# FeatherBME280.net
KiCad netlist of a schematic drawn in EAGLE
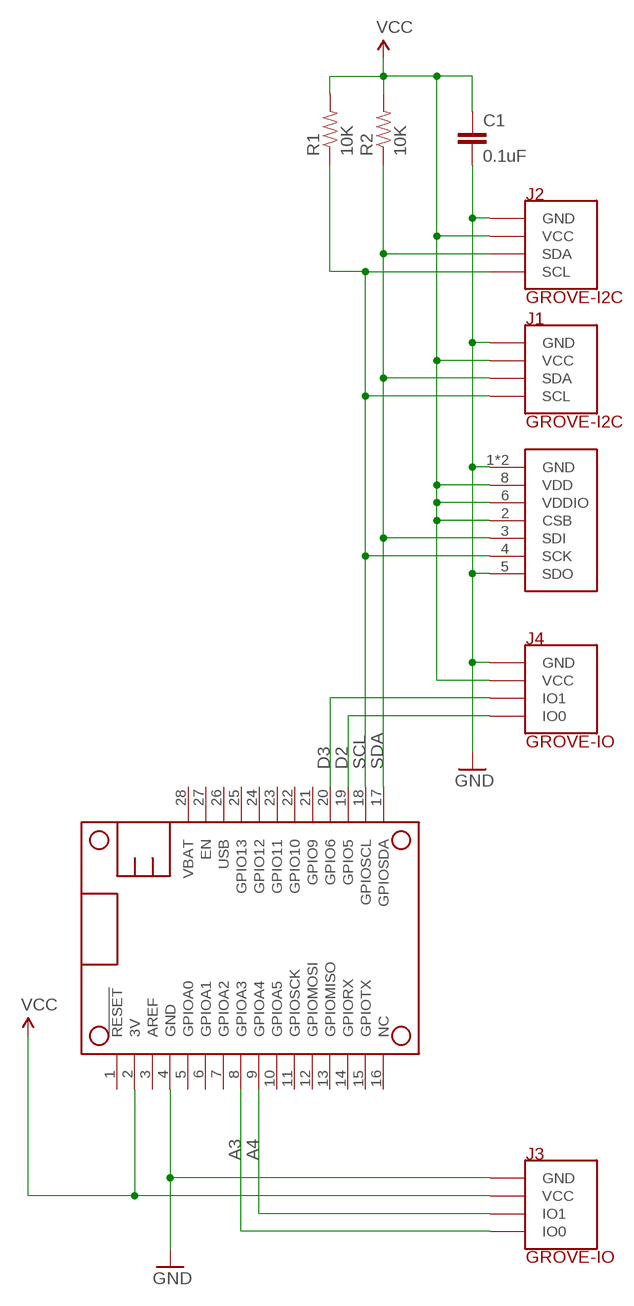
[diagram p0: schematic, sheet 1]

(export (version "E")
  (design (tool "Eeschema 10.0.6"))
  (components
    (comp (ref "C1")
      (value "0.1uF")
      (footprint "eagle-import:0603-CAP")
      (libsource (lib "eagle-import") (part "CAP-0.1UF-0603"))
    )
    (comp (ref "J1")
      (value "GROVE-I2C")
      (footprint "eagle-import:GROVE-VERT-PTH")
      (libsource (lib "eagle-import") (part "GROVE-I2C"))
    )
    (comp (ref "J2")
      (value "GROVE-I2C")
      (footprint "eagle-import:GROVE-VERT-PTH")
      (libsource (lib "eagle-import") (part "GROVE-I2C"))
    )
    (comp (ref "J3")
      (value "GROVE-IO")
      (footprint "eagle-import:GROVE-VERT-PTH")
      (libsource (lib "eagle-import") (part "GROVE-IO"))
    )
    (comp (ref "J4")
      (value "GROVE-IO")
      (footprint "eagle-import:GROVE-VERT-PTH")
      (libsource (lib "eagle-import") (part "GROVE-IO"))
    )
    (comp (ref "MS1")
      (value "FEATHERWING")
      (footprint "eagle-import:FEATHERWING")
      (libsource (lib "eagle-import") (part "FEATHERWING"))
    )
    (comp (ref "R1")
      (value "10K")
      (footprint "eagle-import:0603-RES")
      (libsource (lib "eagle-import") (part "RES-10K-06030603"))
    )
    (comp (ref "R2")
      (value "10K")
      (footprint "eagle-import:0603-RES")
      (libsource (lib "eagle-import") (part "RES-10K-06030603"))
    )
    (comp (ref "U$1")
      (value "BME280")
      (footprint "eagle-import:BME280")
      (libsource (lib "eagle-import") (part "BME280"))
    )
  )
  (nets
    (net (code "1") (name "/A3") (class "Default")
      (node (ref "J3") (pin "1") (pinfunction "IO0_1") (pintype "passive"))
      (node (ref "MS1") (pin "8") (pinfunction "GPIOA3_8") (pintype "bidirectional"))
    )
    (net (code "2") (name "/A4") (class "Default")
      (node (ref "J3") (pin "2") (pinfunction "IO1_2") (pintype "passive"))
      (node (ref "MS1") (pin "9") (pinfunction "GPIOA4_9") (pintype "bidirectional"))
    )
    (net (code "3") (name "/D2") (class "Default")
      (node (ref "J4") (pin "1") (pinfunction "IO0_1") (pintype "passive"))
      (node (ref "MS1") (pin "19") (pinfunction "GPIO5_19") (pintype "bidirectional"))
    )
    (net (code "4") (name "/D3") (class "Default")
      (node (ref "J4") (pin "2") (pinfunction "IO1_2") (pintype "passive"))
      (node (ref "MS1") (pin "20") (pinfunction "GPIO6_20") (pintype "bidirectional"))
    )
    (net (code "5") (name "/SCL") (class "Default")
      (node (ref "J1") (pin "1") (pinfunction "SCL_1") (pintype "passive"))
      (node (ref "J2") (pin "1") (pinfunction "SCL_1") (pintype "passive"))
      (node (ref "MS1") (pin "18") (pinfunction "GPIOSCL_18") (pintype "bidirectional"))
      (node (ref "R1") (pin "1") (pinfunction "1_1") (pintype "passive"))
      (node (ref "U$1") (pin "4") (pinfunction "SCK_4") (pintype "input"))
    )
    (net (code "6") (name "/SDA") (class "Default")
      (node (ref "J1") (pin "2") (pinfunction "SDA_2") (pintype "passive"))
      (node (ref "J2") (pin "2") (pinfunction "SDA_2") (pintype "passive"))
      (node (ref "MS1") (pin "17") (pinfunction "GPIOSDA_17") (pintype "bidirectional"))
      (node (ref "R2") (pin "1") (pinfunction "1_1") (pintype "passive"))
      (node (ref "U$1") (pin "3") (pinfunction "SDI_3") (pintype "bidirectional"))
    )
    (net (code "7") (name "/USB") (class "Default")
      (node (ref "MS1") (pin "26") (pinfunction "USB_26") (pintype "power_in"))
    )
    (net (code "8") (name "/VBAT") (class "Default")
      (node (ref "MS1") (pin "28") (pinfunction "VBAT_28") (pintype "power_in"))
    )
    (net (code "9") (name "GND") (class "Default")
      (node (ref "C1") (pin "2") (pinfunction "2_2") (pintype "passive"))
      (node (ref "J1") (pin "4") (pinfunction "GND_4") (pintype "passive"))
      (node (ref "J2") (pin "4") (pinfunction "GND_4") (pintype "passive"))
      (node (ref "J3") (pin "4") (pinfunction "GND_4") (pintype "passive"))
      (node (ref "J4") (pin "4") (pinfunction "GND_4") (pintype "passive"))
      (node (ref "MS1") (pin "4") (pinfunction "GND_4") (pintype "power_in"))
      (node (ref "U$1") (pin "1") (pinfunction "GND_1") (pintype "power_in"))
      (node (ref "U$1") (pin "5") (pinfunction "SDO_5") (pintype "bidirectional"))
      (node (ref "U$1") (pin "7") (pinfunction "GND_7") (pintype "power_in"))
    )
    (net (code "10") (name "VCC") (class "Default")
      (node (ref "C1") (pin "1") (pinfunction "1_1") (pintype "passive"))
      (node (ref "J1") (pin "3") (pinfunction "VCC_3") (pintype "passive"))
      (node (ref "J2") (pin "3") (pinfunction "VCC_3") (pintype "passive"))
      (node (ref "J3") (pin "3") (pinfunction "VCC_3") (pintype "passive"))
      (node (ref "J4") (pin "3") (pinfunction "VCC_3") (pintype "passive"))
      (node (ref "MS1") (pin "2") (pinfunction "3V_2") (pintype "power_in"))
      (node (ref "R1") (pin "2") (pinfunction "2_2") (pintype "passive"))
      (node (ref "R2") (pin "2") (pinfunction "2_2") (pintype "passive"))
      (node (ref "U$1") (pin "2") (pinfunction "CSB_2") (pintype "input"))
      (node (ref "U$1") (pin "6") (pinfunction "VDDIO_6") (pintype "power_in"))
      (node (ref "U$1") (pin "8") (pinfunction "VDD_8") (pintype "power_in"))
    )
    (net (code "11") (name "unconnected-(MS1-AREF-Pad3)") (class "Default")
      (node (ref "MS1") (pin "3") (pinfunction "AREF_3") (pintype "passive"))
    )
    (net (code "12") (name "unconnected-(MS1-EN-Pad27)") (class "Default")
      (node (ref "MS1") (pin "27") (pinfunction "EN_27") (pintype "passive"))
    )
    (net (code "13") (name "unconnected-(MS1-GPIO9-Pad21)") (class "Default")
      (node (ref "MS1") (pin "21") (pinfunction "GPIO9_21") (pintype "bidirectional"))
    )
    (net (code "14") (name "unconnected-(MS1-GPIO10-Pad22)") (class "Default")
      (node (ref "MS1") (pin "22") (pinfunction "GPIO10_22") (pintype "bidirectional"))
    )
    (net (code "15") (name "unconnected-(MS1-GPIO11-Pad23)") (class "Default")
      (node (ref "MS1") (pin "23") (pinfunction "GPIO11_23") (pintype "bidirectional"))
    )
    (net (code "16") (name "unconnected-(MS1-GPIO12-Pad24)") (class "Default")
      (node (ref "MS1") (pin "24") (pinfunction "GPIO12_24") (pintype "bidirectional"))
    )
    (net (code "17") (name "unconnected-(MS1-GPIO13-Pad25)") (class "Default")
      (node (ref "MS1") (pin "25") (pinfunction "GPIO13_25") (pintype "bidirectional"))
    )
    (net (code "18") (name "unconnected-(MS1-GPIOA0-Pad5)") (class "Default")
      (node (ref "MS1") (pin "5") (pinfunction "GPIOA0_5") (pintype "bidirectional"))
    )
    (net (code "19") (name "unconnected-(MS1-GPIOA1-Pad6)") (class "Default")
      (node (ref "MS1") (pin "6") (pinfunction "GPIOA1_6") (pintype "bidirectional"))
    )
    (net (code "20") (name "unconnected-(MS1-GPIOA2-Pad7)") (class "Default")
      (node (ref "MS1") (pin "7") (pinfunction "GPIOA2_7") (pintype "bidirectional"))
    )
    (net (code "21") (name "unconnected-(MS1-GPIOA5-Pad10)") (class "Default")
      (node (ref "MS1") (pin "10") (pinfunction "GPIOA5_10") (pintype "bidirectional"))
    )
    (net (code "22") (name "unconnected-(MS1-GPIOMISO-Pad13)") (class "Default")
      (node (ref "MS1") (pin "13") (pinfunction "GPIOMISO_13") (pintype "bidirectional"))
    )
    (net (code "23") (name "unconnected-(MS1-GPIOMOSI-Pad12)") (class "Default")
      (node (ref "MS1") (pin "12") (pinfunction "GPIOMOSI_12") (pintype "bidirectional"))
    )
    (net (code "24") (name "unconnected-(MS1-GPIORX-Pad14)") (class "Default")
      (node (ref "MS1") (pin "14") (pinfunction "GPIORX_14") (pintype "bidirectional"))
    )
    (net (code "25") (name "unconnected-(MS1-GPIOSCK-Pad11)") (class "Default")
      (node (ref "MS1") (pin "11") (pinfunction "GPIOSCK_11") (pintype "bidirectional"))
    )
    (net (code "26") (name "unconnected-(MS1-GPIOTX-Pad15)") (class "Default")
      (node (ref "MS1") (pin "15") (pinfunction "GPIOTX_15") (pintype "bidirectional"))
    )
    (net (code "27") (name "unconnected-(MS1-NC-Pad16)") (class "Default")
      (node (ref "MS1") (pin "16") (pinfunction "NC_16") (pintype "passive"))
    )
    (net (code "28") (name "unconnected-(MS1-~{RESET}-Pad1)") (class "Default")
      (node (ref "MS1") (pin "1") (pinfunction "~{RESET}_1") (pintype "input"))
    )
  )
)
